# BME680-Breakout_v11.net
KiCad netlist of a schematic drawn in EAGLE
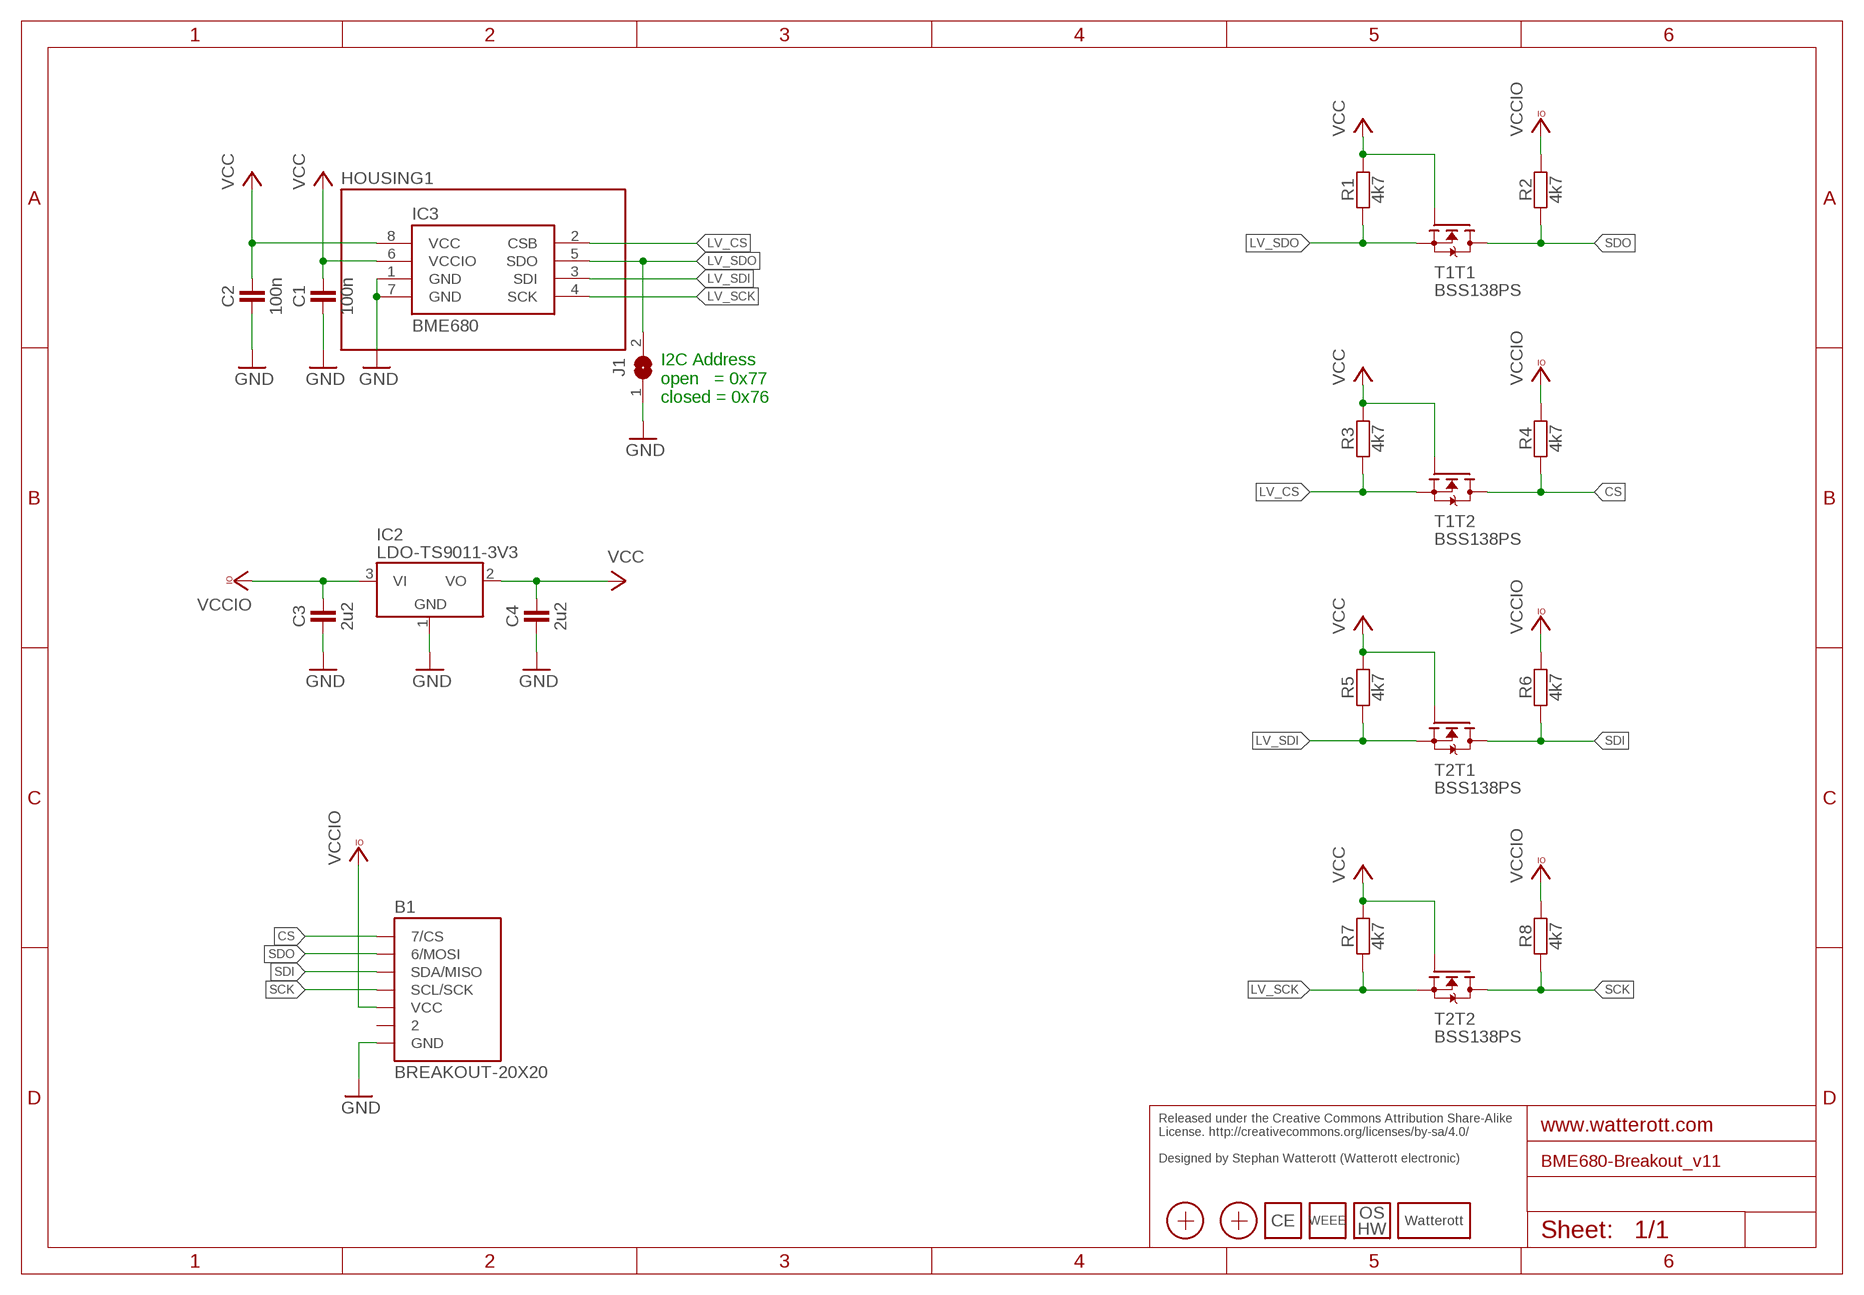
[diagram p0: schematic, sheet 1]

(export (version "E")
  (design (tool "Eeschema 10.0.6"))
  (components
    (comp (ref "B1")
      (value "BREAKOUT-20X20")
      (footprint "eagle-import:BREAKOUT-20X20")
      (libsource (lib "eagle-import") (part "BREAKOUT-20X20"))
    )
    (comp (ref "C1")
      (value "100n")
      (footprint "eagle-import:C0402")
      (libsource (lib "eagle-import") (part "CAPACITOR-0402"))
    )
    (comp (ref "C2")
      (value "100n")
      (footprint "eagle-import:C0402")
      (libsource (lib "eagle-import") (part "CAPACITOR-0402"))
    )
    (comp (ref "C3")
      (value "2u2")
      (footprint "eagle-import:C0402")
      (libsource (lib "eagle-import") (part "CAPACITOR-0402"))
    )
    (comp (ref "C4")
      (value "2u2")
      (footprint "eagle-import:C0402")
      (libsource (lib "eagle-import") (part "CAPACITOR-0402"))
    )
    (comp (ref "HOUSING1")
      (value "SF2")
      (footprint "eagle-import:SF2")
      (libsource (lib "eagle-import") (part "SF2"))
    )
    (comp (ref "IC2")
      (value "LDO-TS9011-3V3")
      (footprint "eagle-import:SOT23")
      (libsource (lib "eagle-import") (part "LDO-TS9011-3V3"))
    )
    (comp (ref "IC3")
      (value "BME680")
      (footprint "eagle-import:BME680")
      (libsource (lib "eagle-import") (part "BME680"))
    )
    (comp (ref "J1")
      (value "JUMPER2-0603")
      (footprint "eagle-import:JUMPER2-0603")
      (libsource (lib "eagle-import") (part "JUMPER2-0603"))
    )
    (comp (ref "LOGO3")
      (value "LOGO_CE-2")
      (footprint "eagle-import:CE_2MM")
      (libsource (lib "eagle-import") (part "LOGO_CE-2"))
    )
    (comp (ref "LOGO4")
      (value "LOGO_WEEE-4")
      (footprint "eagle-import:WEEE_4MM")
      (libsource (lib "eagle-import") (part "LOGO_WEEE-4"))
    )
    (comp (ref "LOGO5")
      (value "LOGO_OSHW-2")
      (footprint "eagle-import:OSHW_2MM")
      (libsource (lib "eagle-import") (part "LOGO_OSHW-2"))
    )
    (comp (ref "LOGO6")
      (value "LOGO_SPARK-2")
      (footprint "eagle-import:SPARK_2MM")
      (libsource (lib "eagle-import") (part "LOGO_SPARK-2"))
    )
    (comp (ref "R1")
      (value "4k7")
      (footprint "eagle-import:C0402")
      (libsource (lib "eagle-import") (part "RESISTOR-0402"))
    )
    (comp (ref "R2")
      (value "4k7")
      (footprint "eagle-import:C0402")
      (libsource (lib "eagle-import") (part "RESISTOR-0402"))
    )
    (comp (ref "R3")
      (value "4k7")
      (footprint "eagle-import:C0402")
      (libsource (lib "eagle-import") (part "RESISTOR-0402"))
    )
    (comp (ref "R4")
      (value "4k7")
      (footprint "eagle-import:C0402")
      (libsource (lib "eagle-import") (part "RESISTOR-0402"))
    )
    (comp (ref "R5")
      (value "4k7")
      (footprint "eagle-import:C0402")
      (libsource (lib "eagle-import") (part "RESISTOR-0402"))
    )
    (comp (ref "R6")
      (value "4k7")
      (footprint "eagle-import:C0402")
      (libsource (lib "eagle-import") (part "RESISTOR-0402"))
    )
    (comp (ref "R7")
      (value "4k7")
      (footprint "eagle-import:C0402")
      (libsource (lib "eagle-import") (part "RESISTOR-0402"))
    )
    (comp (ref "R8")
      (value "4k7")
      (footprint "eagle-import:C0402")
      (libsource (lib "eagle-import") (part "RESISTOR-0402"))
    )
    (comp (ref "T1")
      (value "BSS138PS")
      (footprint "eagle-import:SOT363")
      (libsource (lib "eagle-import") (part "BSS138PS"))
    )
    (comp (ref "T2")
      (value "BSS138PS")
      (footprint "eagle-import:SOT363")
      (libsource (lib "eagle-import") (part "BSS138PS"))
    )
    (comp (ref "X1")
      (value "PASSER-07")
      (footprint "eagle-import:PASSER_07MM")
      (libsource (lib "eagle-import") (part "PASSER-07"))
    )
    (comp (ref "X2")
      (value "PASSER-07")
      (footprint "eagle-import:PASSER_07MM")
      (libsource (lib "eagle-import") (part "PASSER-07"))
    )
  )
  (nets
    (net (code "1") (name "CS") (class "Default")
      (node (ref "B1") (pin "CS") (pinfunction "7/CS_CS") (pintype "bidirectional"))
      (node (ref "R4") (pin "1") (pinfunction "1_1") (pintype "passive"))
      (node (ref "T1") (pin "3") (pinfunction "D_3") (pintype "passive"))
    )
    (net (code "2") (name "GND") (class "Default")
      (node (ref "B1") (pin "GND") (pinfunction "GND_GND") (pintype "power_in"))
      (node (ref "C1") (pin "1") (pinfunction "1_1") (pintype "passive"))
      (node (ref "C2") (pin "1") (pinfunction "1_1") (pintype "passive"))
      (node (ref "C3") (pin "1") (pinfunction "1_1") (pintype "passive"))
      (node (ref "C4") (pin "1") (pinfunction "1_1") (pintype "passive"))
      (node (ref "IC2") (pin "1") (pinfunction "GND_1") (pintype "passive"))
      (node (ref "IC3") (pin "1") (pinfunction "GND_1") (pintype "power_in"))
      (node (ref "IC3") (pin "7") (pinfunction "GND_7") (pintype "power_in"))
      (node (ref "J1") (pin "1") (pinfunction "1_1") (pintype "passive"))
    )
    (net (code "3") (name "LV_CS") (class "Default")
      (node (ref "IC3") (pin "2") (pinfunction "CSB_2") (pintype "input"))
      (node (ref "R3") (pin "1") (pinfunction "1_1") (pintype "passive"))
      (node (ref "T1") (pin "4") (pinfunction "S_4") (pintype "passive"))
    )
    (net (code "4") (name "LV_SCK") (class "Default")
      (node (ref "IC3") (pin "4") (pinfunction "SCK_4") (pintype "bidirectional"))
      (node (ref "R7") (pin "1") (pinfunction "1_1") (pintype "passive"))
      (node (ref "T2") (pin "4") (pinfunction "S_4") (pintype "passive"))
    )
    (net (code "5") (name "LV_SDI") (class "Default")
      (node (ref "IC3") (pin "3") (pinfunction "SDI_3") (pintype "bidirectional"))
      (node (ref "R5") (pin "1") (pinfunction "1_1") (pintype "passive"))
      (node (ref "T2") (pin "1") (pinfunction "S_1") (pintype "passive"))
    )
    (net (code "6") (name "LV_SDO") (class "Default")
      (node (ref "IC3") (pin "5") (pinfunction "SDO_5") (pintype "bidirectional"))
      (node (ref "J1") (pin "2") (pinfunction "2_2") (pintype "passive"))
      (node (ref "R1") (pin "1") (pinfunction "1_1") (pintype "passive"))
      (node (ref "T1") (pin "1") (pinfunction "S_1") (pintype "passive"))
    )
    (net (code "7") (name "SCK") (class "Default")
      (node (ref "B1") (pin "SCL/SCK") (pinfunction "SCL/SCK_SCL/SCK") (pintype "bidirectional"))
      (node (ref "R8") (pin "1") (pinfunction "1_1") (pintype "passive"))
      (node (ref "T2") (pin "3") (pinfunction "D_3") (pintype "passive"))
    )
    (net (code "8") (name "SDI") (class "Default")
      (node (ref "B1") (pin "SDA/MISO") (pinfunction "SDA/MISO_SDA/MISO") (pintype "bidirectional"))
      (node (ref "R6") (pin "1") (pinfunction "1_1") (pintype "passive"))
      (node (ref "T2") (pin "6") (pinfunction "D_6") (pintype "passive"))
    )
    (net (code "9") (name "SDO") (class "Default")
      (node (ref "B1") (pin "MOSI") (pinfunction "6/MOSI_MOSI") (pintype "bidirectional"))
      (node (ref "R2") (pin "1") (pinfunction "1_1") (pintype "passive"))
      (node (ref "T1") (pin "6") (pinfunction "D_6") (pintype "passive"))
    )
    (net (code "10") (name "VCC") (class "Default")
      (node (ref "C1") (pin "2") (pinfunction "2_2") (pintype "passive"))
      (node (ref "C2") (pin "2") (pinfunction "2_2") (pintype "passive"))
      (node (ref "C4") (pin "2") (pinfunction "2_2") (pintype "passive"))
      (node (ref "IC2") (pin "2") (pinfunction "VO_2") (pintype "passive"))
      (node (ref "IC3") (pin "6") (pinfunction "VCCIO_6") (pintype "power_in"))
      (node (ref "IC3") (pin "8") (pinfunction "VCC_8") (pintype "power_in"))
      (node (ref "R1") (pin "2") (pinfunction "2_2") (pintype "passive"))
      (node (ref "R3") (pin "2") (pinfunction "2_2") (pintype "passive"))
      (node (ref "R5") (pin "2") (pinfunction "2_2") (pintype "passive"))
      (node (ref "R7") (pin "2") (pinfunction "2_2") (pintype "passive"))
      (node (ref "T1") (pin "2") (pinfunction "G_2") (pintype "passive"))
      (node (ref "T1") (pin "5") (pinfunction "G_5") (pintype "passive"))
      (node (ref "T2") (pin "2") (pinfunction "G_2") (pintype "passive"))
      (node (ref "T2") (pin "5") (pinfunction "G_5") (pintype "passive"))
    )
    (net (code "11") (name "VCCIO") (class "Default")
      (node (ref "B1") (pin "VCC") (pinfunction "VCC_VCC") (pintype "power_in"))
      (node (ref "C3") (pin "2") (pinfunction "2_2") (pintype "passive"))
      (node (ref "IC2") (pin "3") (pinfunction "VI_3") (pintype "input"))
      (node (ref "R2") (pin "2") (pinfunction "2_2") (pintype "passive"))
      (node (ref "R4") (pin "2") (pinfunction "2_2") (pintype "passive"))
      (node (ref "R6") (pin "2") (pinfunction "2_2") (pintype "passive"))
      (node (ref "R8") (pin "2") (pinfunction "2_2") (pintype "passive"))
    )
    (net (code "12") (name "unconnected-(B1-Pad2)") (class "Default")
      (node (ref "B1") (pin "2") (pinfunction "2_2") (pintype "bidirectional"))
    )
  )
)
